# CanBus-Gartenbewaesserung.net
KiCad netlist of a schematic drawn in EAGLE
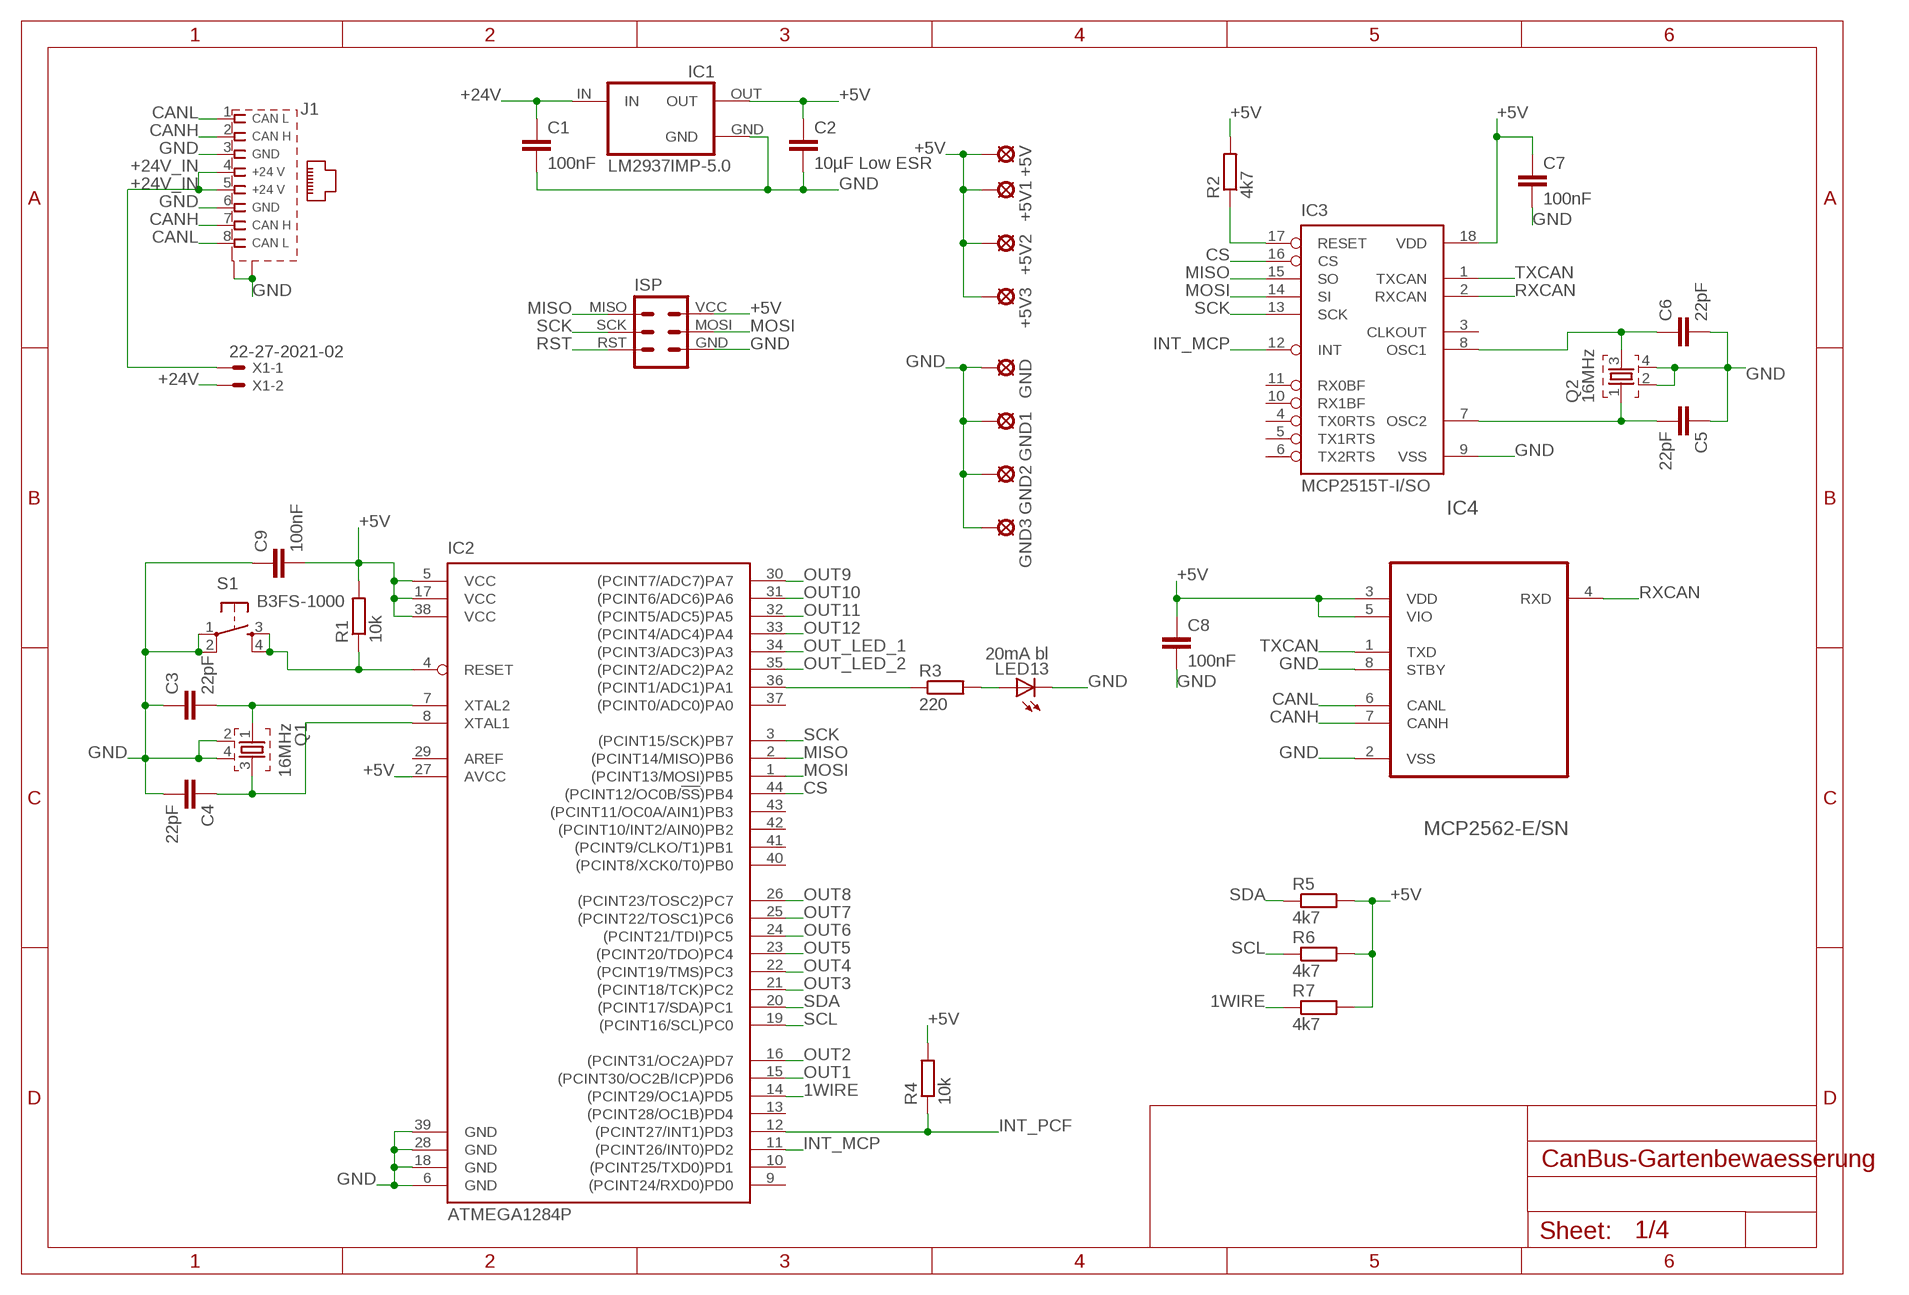
[diagram p0: schematic, sheet 1]
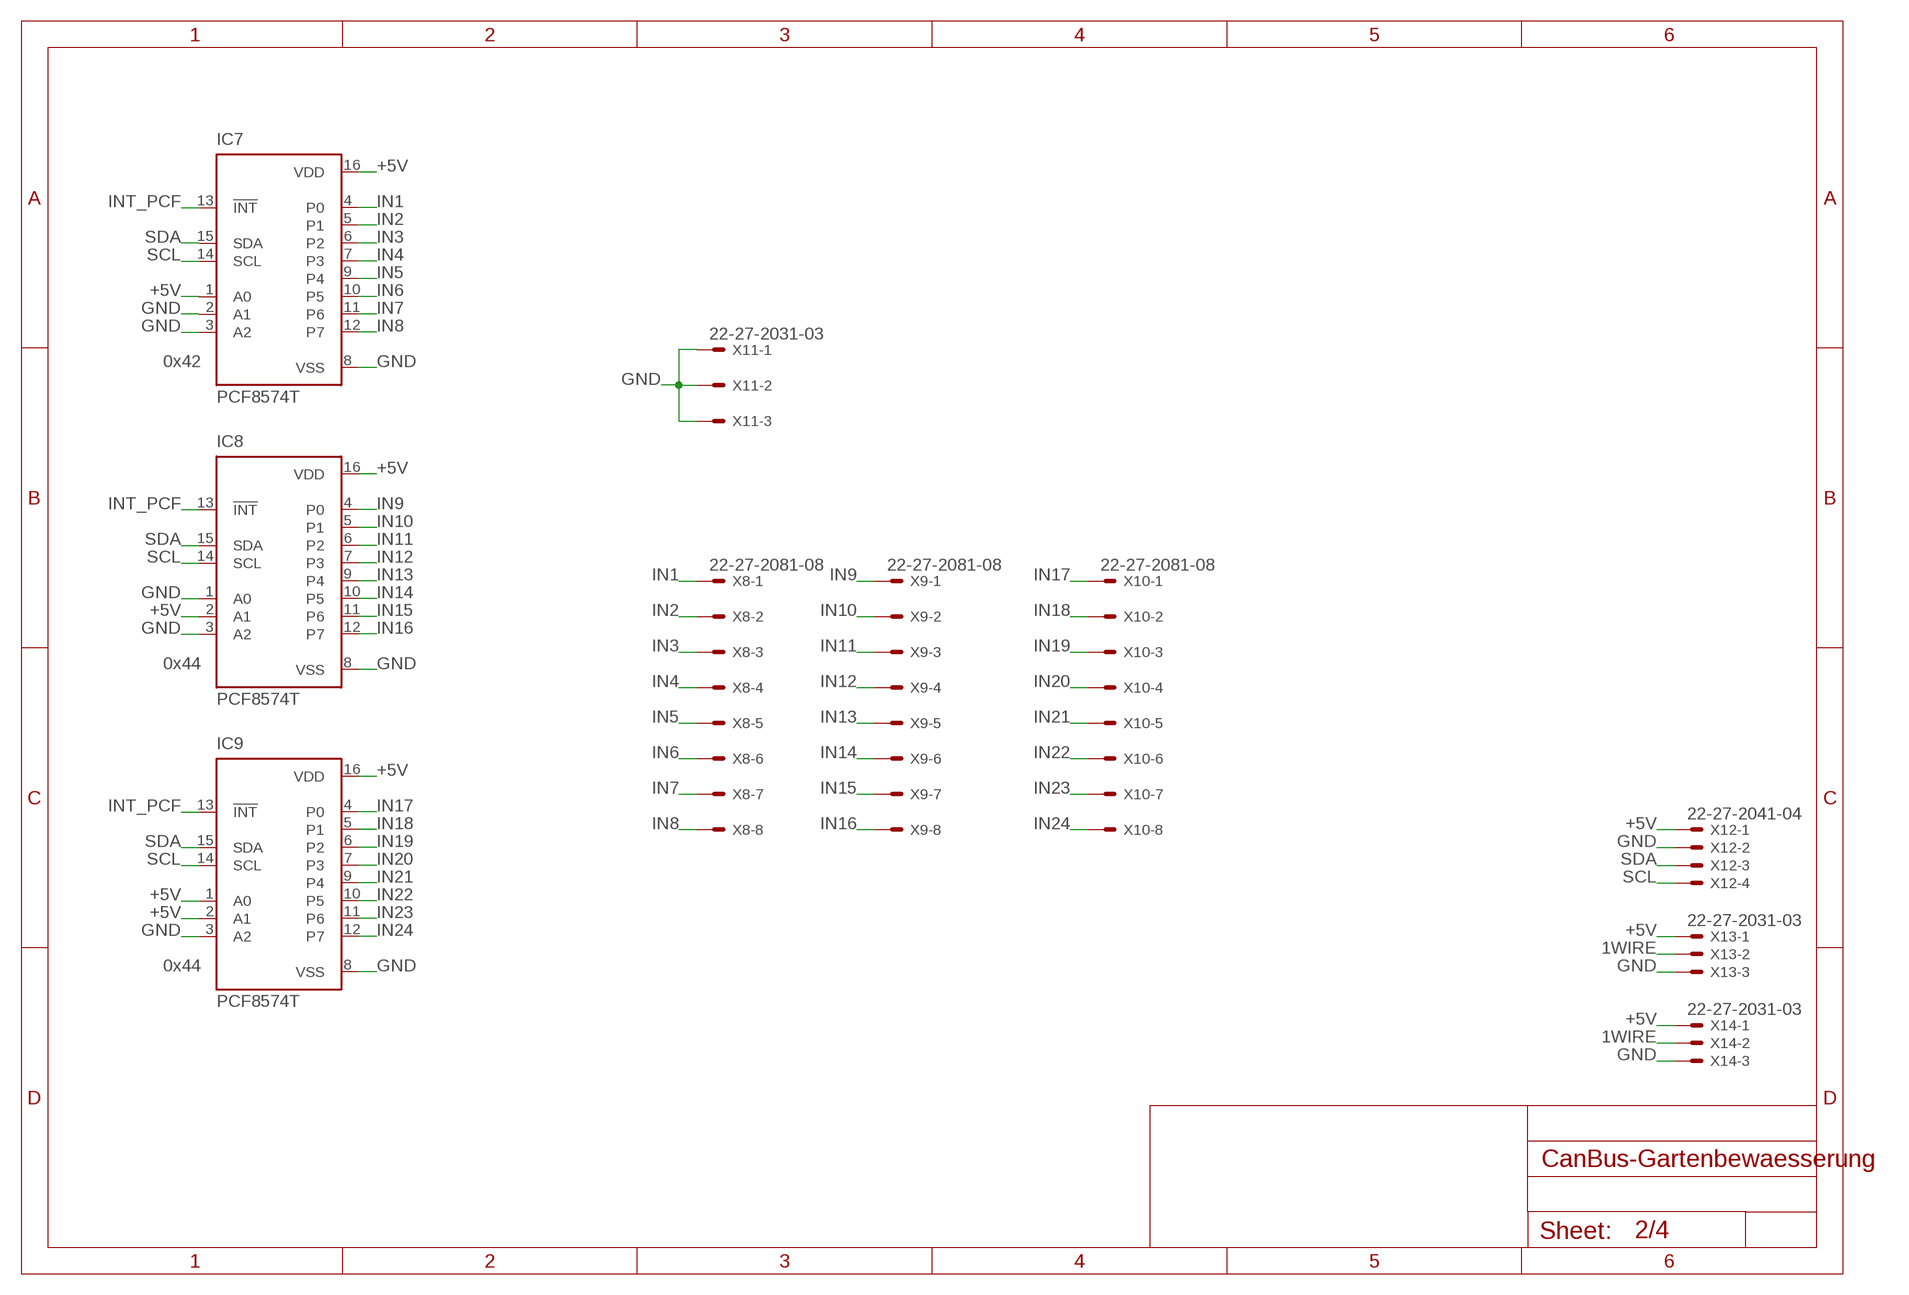
[diagram p1: schematic, sheet 2]
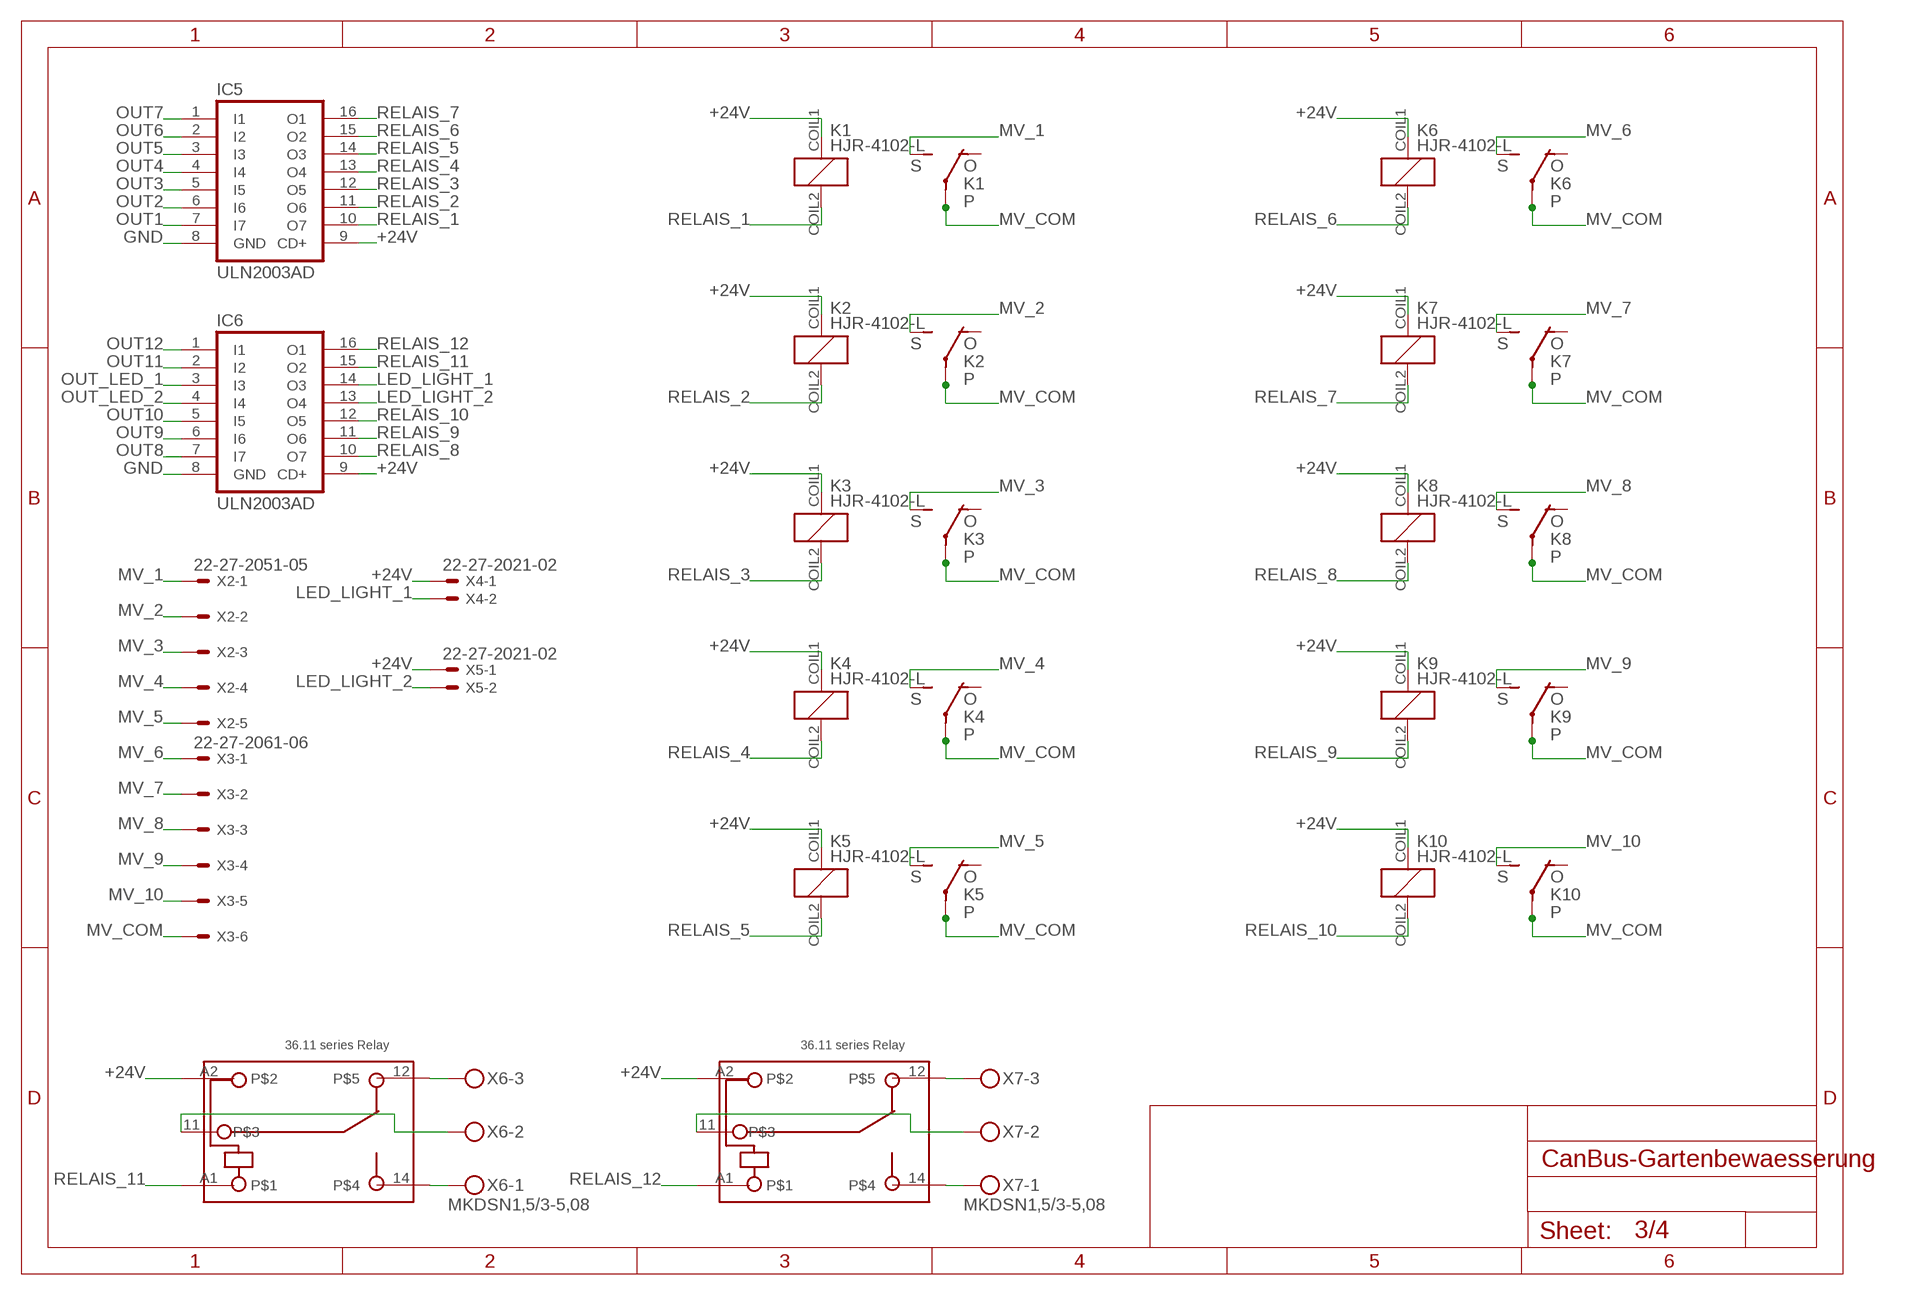
[diagram p2: schematic, sheet 3]
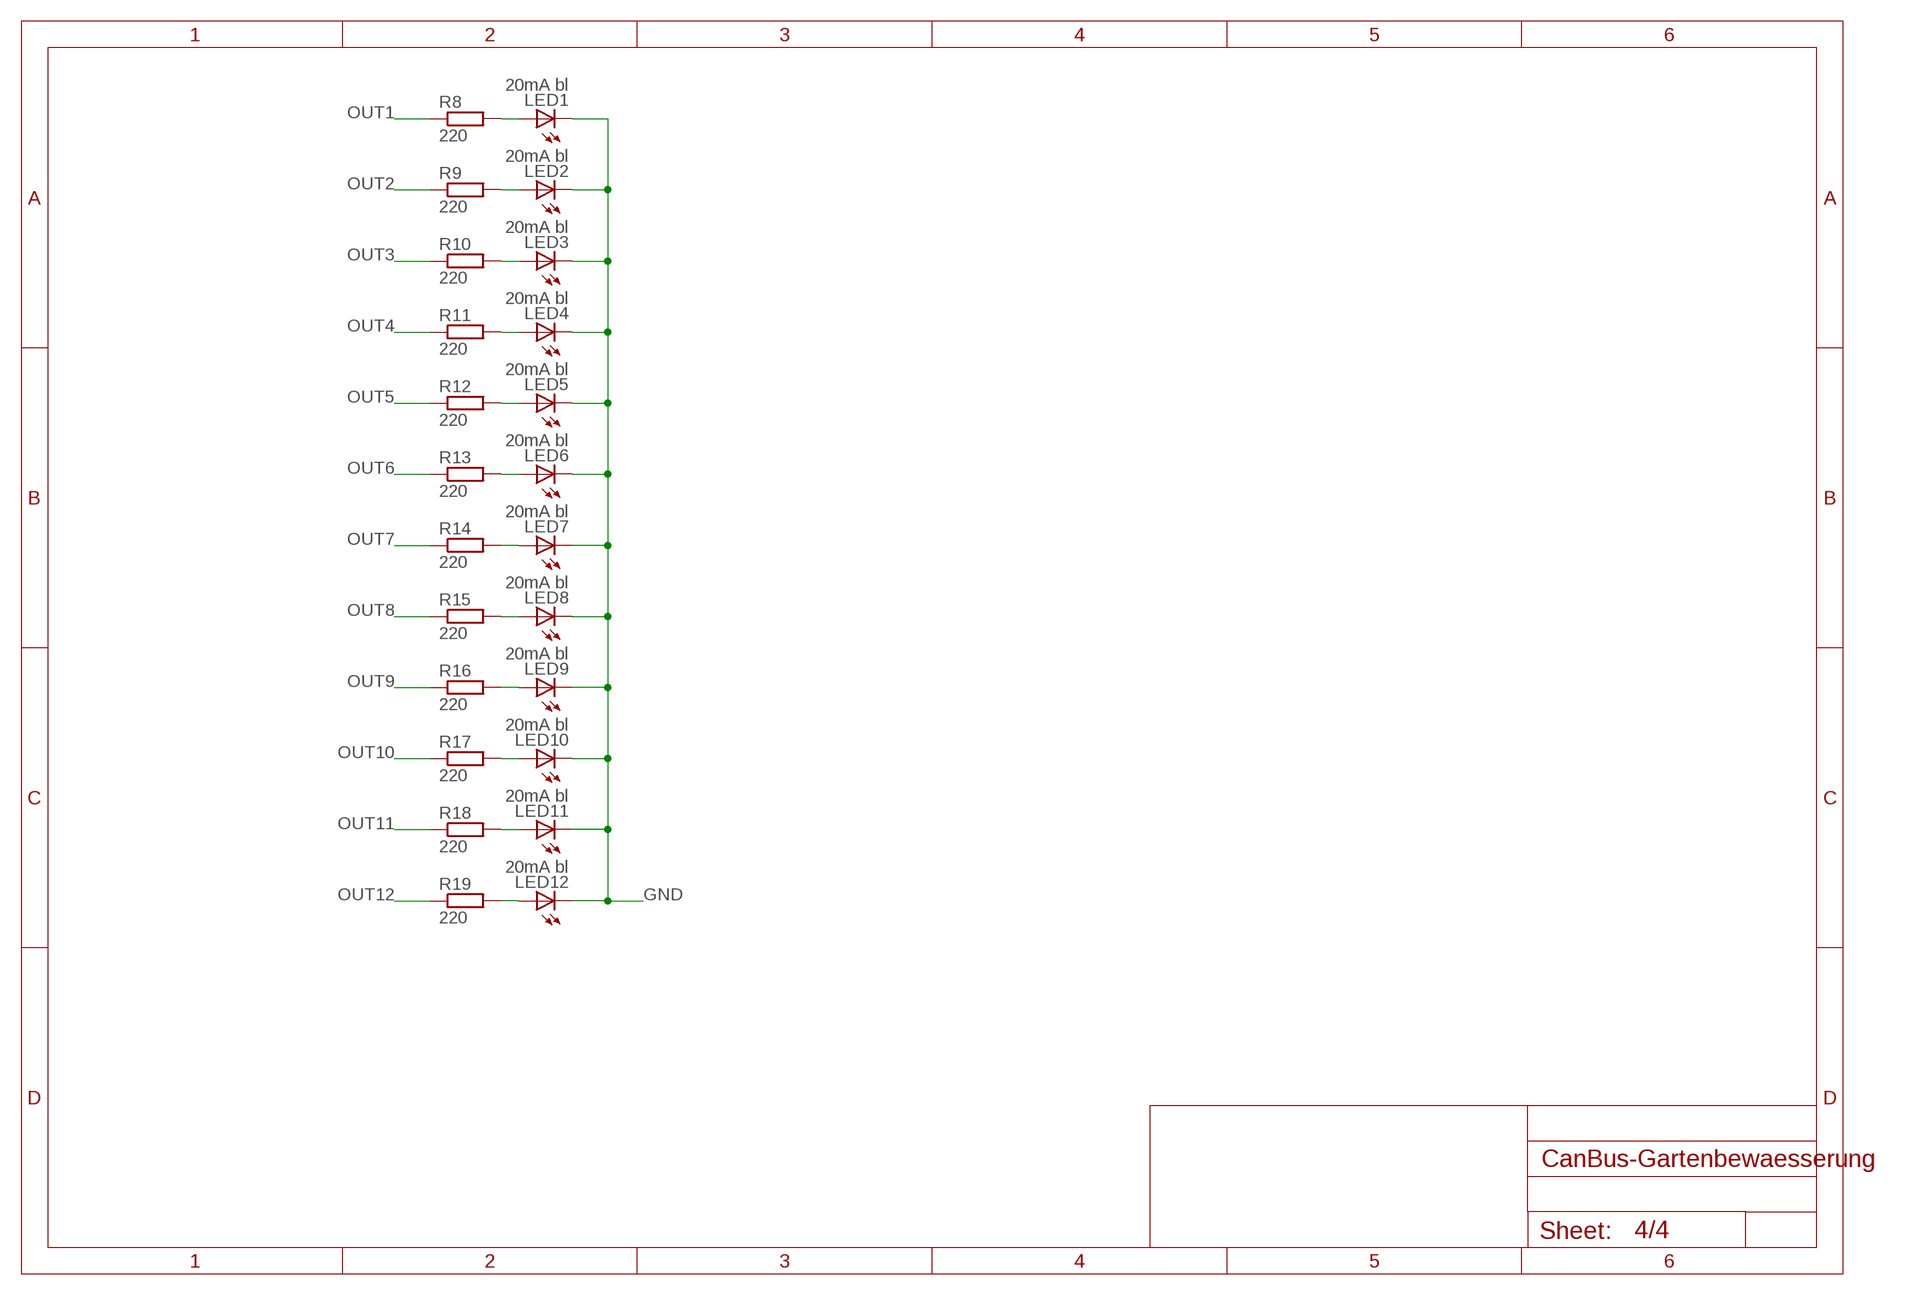
[diagram p3: schematic, sheet 4]

(export (version "E")
  (design (tool "Eeschema 10.0.6"))
  (components
    (comp (ref "LED1")
      (value "20mA bl")
      (footprint "eagle-import:CHIPLED_0805")
      (libsource (lib "eagle-import") (part "LEDCHIPLED_0805"))
    )
    (comp (ref "LED2")
      (value "20mA bl")
      (footprint "eagle-import:CHIPLED_0805")
      (libsource (lib "eagle-import") (part "LEDCHIPLED_0805"))
    )
    (comp (ref "LED3")
      (value "20mA bl")
      (footprint "eagle-import:CHIPLED_0805")
      (libsource (lib "eagle-import") (part "LEDCHIPLED_0805"))
    )
    (comp (ref "LED4")
      (value "20mA bl")
      (footprint "eagle-import:CHIPLED_0805")
      (libsource (lib "eagle-import") (part "LEDCHIPLED_0805"))
    )
    (comp (ref "LED5")
      (value "20mA bl")
      (footprint "eagle-import:CHIPLED_0805")
      (libsource (lib "eagle-import") (part "LEDCHIPLED_0805"))
    )
    (comp (ref "LED6")
      (value "20mA bl")
      (footprint "eagle-import:CHIPLED_0805")
      (libsource (lib "eagle-import") (part "LEDCHIPLED_0805"))
    )
    (comp (ref "LED7")
      (value "20mA bl")
      (footprint "eagle-import:CHIPLED_0805")
      (libsource (lib "eagle-import") (part "LEDCHIPLED_0805"))
    )
    (comp (ref "LED8")
      (value "20mA bl")
      (footprint "eagle-import:CHIPLED_0805")
      (libsource (lib "eagle-import") (part "LEDCHIPLED_0805"))
    )
    (comp (ref "LED9")
      (value "20mA bl")
      (footprint "eagle-import:CHIPLED_0805")
      (libsource (lib "eagle-import") (part "LEDCHIPLED_0805"))
    )
    (comp (ref "LED10")
      (value "20mA bl")
      (footprint "eagle-import:CHIPLED_0805")
      (libsource (lib "eagle-import") (part "LEDCHIPLED_0805"))
    )
    (comp (ref "LED11")
      (value "20mA bl")
      (footprint "eagle-import:CHIPLED_0805")
      (libsource (lib "eagle-import") (part "LEDCHIPLED_0805"))
    )
    (comp (ref "LED12")
      (value "20mA bl")
      (footprint "eagle-import:CHIPLED_0805")
      (libsource (lib "eagle-import") (part "LEDCHIPLED_0805"))
    )
    (comp (ref "R8")
      (value "220")
      (footprint "eagle-import:R0805")
      (libsource (lib "eagle-import") (part "R-EU_R0805"))
    )
    (comp (ref "R9")
      (value "220")
      (footprint "eagle-import:R0805")
      (libsource (lib "eagle-import") (part "R-EU_R0805"))
    )
    (comp (ref "R10")
      (value "220")
      (footprint "eagle-import:R0805")
      (libsource (lib "eagle-import") (part "R-EU_R0805"))
    )
    (comp (ref "R11")
      (value "220")
      (footprint "eagle-import:R0805")
      (libsource (lib "eagle-import") (part "R-EU_R0805"))
    )
    (comp (ref "R12")
      (value "220")
      (footprint "eagle-import:R0805")
      (libsource (lib "eagle-import") (part "R-EU_R0805"))
    )
    (comp (ref "R13")
      (value "220")
      (footprint "eagle-import:R0805")
      (libsource (lib "eagle-import") (part "R-EU_R0805"))
    )
    (comp (ref "R14")
      (value "220")
      (footprint "eagle-import:R0805")
      (libsource (lib "eagle-import") (part "R-EU_R0805"))
    )
    (comp (ref "R15")
      (value "220")
      (footprint "eagle-import:R0805")
      (libsource (lib "eagle-import") (part "R-EU_R0805"))
    )
    (comp (ref "R16")
      (value "220")
      (footprint "eagle-import:R0805")
      (libsource (lib "eagle-import") (part "R-EU_R0805"))
    )
    (comp (ref "R17")
      (value "220")
      (footprint "eagle-import:R0805")
      (libsource (lib "eagle-import") (part "R-EU_R0805"))
    )
    (comp (ref "R18")
      (value "220")
      (footprint "eagle-import:R0805")
      (libsource (lib "eagle-import") (part "R-EU_R0805"))
    )
    (comp (ref "R19")
      (value "220")
      (footprint "eagle-import:R0805")
      (libsource (lib "eagle-import") (part "R-EU_R0805"))
    )
    (comp (ref "IC7")
      (value "PCF8574T")
      (footprint "eagle-import:SO16W")
      (fields (field (name "MPN") "PCF8574T/3,512"))
      (libsource (lib "eagle-import") (part "PCF8574T"))
    )
    (comp (ref "IC8")
      (value "PCF8574T")
      (footprint "eagle-import:SO16W")
      (fields (field (name "MPN") "PCF8574T/3,512"))
      (libsource (lib "eagle-import") (part "PCF8574T"))
    )
    (comp (ref "IC9")
      (value "PCF8574T")
      (footprint "eagle-import:SO16W")
      (fields (field (name "MPN") "PCF8574T/3,512"))
      (libsource (lib "eagle-import") (part "PCF8574T"))
    )
    (comp (ref "X8")
      (value "22-27-2081-08")
      (footprint "eagle-import:6410-08")
      (libsource (lib "eagle-import") (part "22-?-0827-2081"))
    )
    (comp (ref "X9")
      (value "22-27-2081-08")
      (footprint "eagle-import:6410-08")
      (libsource (lib "eagle-import") (part "22-?-0827-2081"))
    )
    (comp (ref "X10")
      (value "22-27-2081-08")
      (footprint "eagle-import:6410-08")
      (libsource (lib "eagle-import") (part "22-?-0827-2081"))
    )
    (comp (ref "X11")
      (value "22-27-2031-03")
      (footprint "eagle-import:6410-03")
      (libsource (lib "eagle-import") (part "22-?-0327-2031"))
    )
    (comp (ref "X12")
      (value "22-27-2041-04")
      (footprint "eagle-import:6410-04")
      (libsource (lib "eagle-import") (part "22-?-0427-2041"))
    )
    (comp (ref "X13")
      (value "22-27-2031-03")
      (footprint "eagle-import:6410-03")
      (libsource (lib "eagle-import") (part "22-?-0327-2031"))
    )
    (comp (ref "X14")
      (value "22-27-2031-03")
      (footprint "eagle-import:6410-03")
      (libsource (lib "eagle-import") (part "22-?-0327-2031"))
    )
    (comp (ref "+5V")
      (value "LSP13")
      (footprint "eagle-import:LSP13")
      (libsource (lib "eagle-import") (part "LSP13"))
    )
    (comp (ref "+5V1")
      (value "LSP13")
      (footprint "eagle-import:LSP13")
      (libsource (lib "eagle-import") (part "LSP13"))
    )
    (comp (ref "+5V2")
      (value "LSP13")
      (footprint "eagle-import:LSP13")
      (libsource (lib "eagle-import") (part "LSP13"))
    )
    (comp (ref "+5V3")
      (value "LSP13")
      (footprint "eagle-import:LSP13")
      (libsource (lib "eagle-import") (part "LSP13"))
    )
    (comp (ref "C1")
      (value "100nF")
      (footprint "eagle-import:C0805")
      (libsource (lib "eagle-import") (part "C-EUC0805"))
    )
    (comp (ref "C2")
      (value "10µF Low ESR")
      (footprint "eagle-import:C0805")
      (libsource (lib "eagle-import") (part "C-EUC0805"))
    )
    (comp (ref "C3")
      (value "22pF")
      (footprint "eagle-import:C0805")
      (libsource (lib "eagle-import") (part "C-EUC0805"))
    )
    (comp (ref "C4")
      (value "22pF")
      (footprint "eagle-import:C0805")
      (libsource (lib "eagle-import") (part "C-EUC0805"))
    )
    (comp (ref "C5")
      (value "22pF")
      (footprint "eagle-import:C0805")
      (libsource (lib "eagle-import") (part "C-EUC0805"))
    )
    (comp (ref "C6")
      (value "22pF")
      (footprint "eagle-import:C0805")
      (libsource (lib "eagle-import") (part "C-EUC0805"))
    )
    (comp (ref "C7")
      (value "100nF")
      (footprint "eagle-import:C0805")
      (libsource (lib "eagle-import") (part "C-EUC0805"))
    )
    (comp (ref "C8")
      (value "100nF")
      (footprint "eagle-import:C0805")
      (libsource (lib "eagle-import") (part "C-EUC0805"))
    )
    (comp (ref "C9")
      (value "100nF")
      (footprint "eagle-import:C0805")
      (libsource (lib "eagle-import") (part "C-EUC0805"))
    )
    (comp (ref "GND")
      (value "LSP13")
      (footprint "eagle-import:LSP13")
      (libsource (lib "eagle-import") (part "LSP13"))
    )
    (comp (ref "GND1")
      (value "LSP13")
      (footprint "eagle-import:LSP13")
      (libsource (lib "eagle-import") (part "LSP13"))
    )
    (comp (ref "GND2")
      (value "LSP13")
      (footprint "eagle-import:LSP13")
      (libsource (lib "eagle-import") (part "LSP13"))
    )
    (comp (ref "GND3")
      (value "LSP13")
      (footprint "eagle-import:LSP13")
      (libsource (lib "eagle-import") (part "LSP13"))
    )
    (comp (ref "IC1")
      (value "LM2937IMP-5.0")
      (footprint "eagle-import:SOT223")
      (libsource (lib "eagle-import") (part "LM2937IMP-5.0"))
    )
    (comp (ref "IC2")
      (value "ATMEGA1284P")
      (footprint "eagle-import:TQFP44")
      (fields (field (name "MPN") "ATMEGA644PV-10AU"))
      (libsource (lib "eagle-import") (part "ATMEGA644A"))
    )
    (comp (ref "IC3")
      (value "MCP2515T-I/SO")
      (footprint "eagle-import:SO18L")
      (libsource (lib "eagle-import") (part "MCP2515T-I/SO"))
    )
    (comp (ref "IC4")
      (value "MCP2562-E/SN")
      (footprint "eagle-import:SO08")
      (libsource (lib "eagle-import") (part "MCP2562-E/SN"))
    )
    (comp (ref "ISP")
      (value "ISPVIAS-ONLY-1.27MM")
      (footprint "eagle-import:ISP-VIAS-ONLY-1.27MM")
      (libsource (lib "eagle-import") (part "ISPVIAS-ONLY-1.27MM"))
    )
    (comp (ref "J1")
      (value "RJ45-CAN")
      (footprint "eagle-import:MEBP_8-8G")
      (libsource (lib "eagle-import") (part "RJ45-CAN"))
    )
    (comp (ref "LED13")
      (value "20mA bl")
      (footprint "eagle-import:CHIPLED_0805")
      (libsource (lib "eagle-import") (part "LEDCHIPLED_0805"))
    )
    (comp (ref "Q1")
      (value "16MHz")
      (footprint "eagle-import:MJ-5X3.2")
      (libsource (lib "eagle-import") (part "EUROQUARTZ-MMJ"))
    )
    (comp (ref "Q2")
      (value "16MHz")
      (footprint "eagle-import:MJ-5X3.2")
      (libsource (lib "eagle-import") (part "EUROQUARTZ-MMJ"))
    )
    (comp (ref "R1")
      (value "10k")
      (footprint "eagle-import:R0805")
      (libsource (lib "eagle-import") (part "R-EU_R0805"))
    )
    (comp (ref "R2")
      (value "4k7")
      (footprint "eagle-import:R0805")
      (libsource (lib "eagle-import") (part "R-EU_R0805"))
    )
    (comp (ref "R3")
      (value "220")
      (footprint "eagle-import:R0805")
      (libsource (lib "eagle-import") (part "R-EU_R0805"))
    )
    (comp (ref "R4")
      (value "10k")
      (footprint "eagle-import:R0805")
      (libsource (lib "eagle-import") (part "R-EU_R0805"))
    )
    (comp (ref "R5")
      (value "4k7")
      (footprint "eagle-import:R0805")
      (libsource (lib "eagle-import") (part "R-EU_R0805"))
    )
    (comp (ref "R6")
      (value "4k7")
      (footprint "eagle-import:R0805")
      (libsource (lib "eagle-import") (part "R-EU_R0805"))
    )
    (comp (ref "R7")
      (value "4k7")
      (footprint "eagle-import:R0805")
      (libsource (lib "eagle-import") (part "R-EU_R0805"))
    )
    (comp (ref "S1")
      (value "B3FS-1000")
      (footprint "eagle-import:B3FS-1000")
      (libsource (lib "eagle-import") (part "B3FS-1000"))
    )
    (comp (ref "X1")
      (value "22-27-2021-02")
      (footprint "eagle-import:6410-02")
      (libsource (lib "eagle-import") (part "22-?-0227-2021"))
    )
    (comp (ref "IC5")
      (value "ULN2003AD")
      (footprint "eagle-import:SO16")
      (libsource (lib "eagle-import") (part "ULN2003AD"))
    )
    (comp (ref "IC6")
      (value "ULN2003AD")
      (footprint "eagle-import:SO16")
      (libsource (lib "eagle-import") (part "ULN2003AD"))
    )
    (comp (ref "K1")
      (value "HJR-4102-L")
      (footprint "eagle-import:HJR4102")
      (libsource (lib "eagle-import") (part "HJR-4102-L"))
    )
    (comp (ref "K2")
      (value "HJR-4102-L")
      (footprint "eagle-import:HJR4102")
      (libsource (lib "eagle-import") (part "HJR-4102-L"))
    )
    (comp (ref "K3")
      (value "HJR-4102-L")
      (footprint "eagle-import:HJR4102")
      (libsource (lib "eagle-import") (part "HJR-4102-L"))
    )
    (comp (ref "K4")
      (value "HJR-4102-L")
      (footprint "eagle-import:HJR4102")
      (libsource (lib "eagle-import") (part "HJR-4102-L"))
    )
    (comp (ref "K5")
      (value "HJR-4102-L")
      (footprint "eagle-import:HJR4102")
      (libsource (lib "eagle-import") (part "HJR-4102-L"))
    )
    (comp (ref "K6")
      (value "HJR-4102-L")
      (footprint "eagle-import:HJR4102")
      (libsource (lib "eagle-import") (part "HJR-4102-L"))
    )
    (comp (ref "K7")
      (value "HJR-4102-L")
      (footprint "eagle-import:HJR4102")
      (libsource (lib "eagle-import") (part "HJR-4102-L"))
    )
    (comp (ref "K8")
      (value "HJR-4102-L")
      (footprint "eagle-import:HJR4102")
      (libsource (lib "eagle-import") (part "HJR-4102-L"))
    )
    (comp (ref "K9")
      (value "HJR-4102-L")
      (footprint "eagle-import:HJR4102")
      (libsource (lib "eagle-import") (part "HJR-4102-L"))
    )
    (comp (ref "K10")
      (value "HJR-4102-L")
      (footprint "eagle-import:HJR4102")
      (libsource (lib "eagle-import") (part "HJR-4102-L"))
    )
    (comp (ref "K11")
      (value "36.11")
      (footprint "eagle-import:36.11")
      (libsource (lib "eagle-import") (part "36.11"))
    )
    (comp (ref "K12")
      (value "36.11")
      (footprint "eagle-import:36.11")
      (libsource (lib "eagle-import") (part "36.11"))
    )
    (comp (ref "X2")
      (value "22-27-2051-05")
      (footprint "eagle-import:6410-05")
      (libsource (lib "eagle-import") (part "22-?-0527-2051"))
    )
    (comp (ref "X3")
      (value "22-27-2061-06")
      (footprint "eagle-import:6410-06")
      (libsource (lib "eagle-import") (part "22-?-0627-2061"))
    )
    (comp (ref "X4")
      (value "22-27-2021-02")
      (footprint "eagle-import:6410-02")
      (libsource (lib "eagle-import") (part "22-?-0227-2021"))
    )
    (comp (ref "X5")
      (value "22-27-2021-02")
      (footprint "eagle-import:6410-02")
      (libsource (lib "eagle-import") (part "22-?-0227-2021"))
    )
    (comp (ref "X6")
      (value "MKDSN1,5/3-5,08")
      (footprint "eagle-import:MKDSN1,5_3-5,08")
      (libsource (lib "eagle-import") (part "MKDSN1,5/3-5,08"))
    )
    (comp (ref "X7")
      (value "MKDSN1,5/3-5,08")
      (footprint "eagle-import:MKDSN1,5_3-5,08")
      (libsource (lib "eagle-import") (part "MKDSN1,5/3-5,08"))
    )
  )
  (nets
    (net (code "1") (name "+5V") (class "Default")
      (node (ref "+5V") (pin "MP") (pinfunction "MP_MP") (pintype "passive"))
      (node (ref "+5V1") (pin "MP") (pinfunction "MP_MP") (pintype "passive"))
      (node (ref "+5V2") (pin "MP") (pinfunction "MP_MP") (pintype "passive"))
      (node (ref "+5V3") (pin "MP") (pinfunction "MP_MP") (pintype "passive"))
      (node (ref "C2") (pin "1") (pinfunction "1_1") (pintype "passive"))
      (node (ref "C7") (pin "1") (pinfunction "1_1") (pintype "passive"))
      (node (ref "C8") (pin "1") (pinfunction "1_1") (pintype "passive"))
      (node (ref "C9") (pin "2") (pinfunction "2_2") (pintype "passive"))
      (node (ref "IC1") (pin "OUT") (pinfunction "OUT_OUT") (pintype "output"))
      (node (ref "IC2") (pin "17") (pinfunction "VCC_17") (pintype "power_in"))
      (node (ref "IC2") (pin "27") (pinfunction "AVCC_27") (pintype "power_in"))
      (node (ref "IC2") (pin "38") (pinfunction "VCC_38") (pintype "power_in"))
      (node (ref "IC2") (pin "5") (pinfunction "VCC_5") (pintype "power_in"))
      (node (ref "IC3") (pin "18") (pinfunction "VDD_18") (pintype "power_in"))
      (node (ref "IC4") (pin "3") (pinfunction "VDD_3") (pintype "power_in"))
      (node (ref "IC4") (pin "5") (pinfunction "VIO_5") (pintype "power_in"))
      (node (ref "IC7") (pin "1") (pinfunction "A0_1") (pintype "input"))
      (node (ref "IC7") (pin "16") (pinfunction "VDD_16") (pintype "power_in"))
      (node (ref "IC8") (pin "16") (pinfunction "VDD_16") (pintype "power_in"))
      (node (ref "IC8") (pin "2") (pinfunction "A1_2") (pintype "input"))
      (node (ref "IC9") (pin "1") (pinfunction "A0_1") (pintype "input"))
      (node (ref "IC9") (pin "16") (pinfunction "VDD_16") (pintype "power_in"))
      (node (ref "IC9") (pin "2") (pinfunction "A1_2") (pintype "input"))
      (node (ref "ISP") (pin "VCC") (pinfunction "VCC_VCC") (pintype "passive"))
      (node (ref "R1") (pin "2") (pinfunction "2_2") (pintype "passive"))
      (node (ref "R2") (pin "2") (pinfunction "2_2") (pintype "passive"))
      (node (ref "R4") (pin "2") (pinfunction "2_2") (pintype "passive"))
      (node (ref "R5") (pin "2") (pinfunction "2_2") (pintype "passive"))
      (node (ref "R6") (pin "2") (pinfunction "2_2") (pintype "passive"))
      (node (ref "R7") (pin "2") (pinfunction "2_2") (pintype "passive"))
      (node (ref "X12") (pin "1") (pinfunction "S_1") (pintype "passive"))
      (node (ref "X13") (pin "1") (pinfunction "S_1") (pintype "passive"))
      (node (ref "X14") (pin "1") (pinfunction "S_1") (pintype "passive"))
    )
    (net (code "2") (name "+24V") (class "Default")
      (node (ref "C1") (pin "1") (pinfunction "1_1") (pintype "passive"))
      (node (ref "IC1") (pin "IN") (pinfunction "IN_IN") (pintype "input"))
      (node (ref "IC5") (pin "9") (pinfunction "CD+_9") (pintype "passive"))
      (node (ref "IC6") (pin "9") (pinfunction "CD+_9") (pintype "passive"))
      (node (ref "K1") (pin "COIL1") (pinfunction "1_COIL1") (pintype "passive"))
      (node (ref "K10") (pin "COIL1") (pinfunction "1_COIL1") (pintype "passive"))
      (node (ref "K11") (pin "A2") (pinfunction "P$2_A2") (pintype "passive"))
      (node (ref "K12") (pin "A2") (pinfunction "P$2_A2") (pintype "passive"))
      (node (ref "K2") (pin "COIL1") (pinfunction "1_COIL1") (pintype "passive"))
      (node (ref "K3") (pin "COIL1") (pinfunction "1_COIL1") (pintype "passive"))
      (node (ref "K4") (pin "COIL1") (pinfunction "1_COIL1") (pintype "passive"))
      (node (ref "K5") (pin "COIL1") (pinfunction "1_COIL1") (pintype "passive"))
      (node (ref "K6") (pin "COIL1") (pinfunction "1_COIL1") (pintype "passive"))
      (node (ref "K7") (pin "COIL1") (pinfunction "1_COIL1") (pintype "passive"))
      (node (ref "K8") (pin "COIL1") (pinfunction "1_COIL1") (pintype "passive"))
      (node (ref "K9") (pin "COIL1") (pinfunction "1_COIL1") (pintype "passive"))
      (node (ref "X1") (pin "2") (pinfunction "S_2") (pintype "passive"))
      (node (ref "X4") (pin "1") (pinfunction "S_1") (pintype "passive"))
      (node (ref "X5") (pin "1") (pinfunction "S_1") (pintype "passive"))
    )
    (net (code "3") (name "+24V_IN") (class "Default")
      (node (ref "J1") (pin "4") (pinfunction "4_4") (pintype "passive"))
      (node (ref "J1") (pin "5") (pinfunction "5_5") (pintype "passive"))
      (node (ref "X1") (pin "1") (pinfunction "S_1") (pintype "passive"))
    )
    (net (code "4") (name "1WIRE") (class "Default")
      (node (ref "IC2") (pin "14") (pinfunction "(PCINT29/OC1A)PD5_14") (pintype "bidirectional"))
      (node (ref "R7") (pin "1") (pinfunction "1_1") (pintype "passive"))
      (node (ref "X13") (pin "2") (pinfunction "S_2") (pintype "passive"))
      (node (ref "X14") (pin "2") (pinfunction "S_2") (pintype "passive"))
    )
    (net (code "5") (name "CANH") (class "Default")
      (node (ref "IC4") (pin "7") (pinfunction "CANH_7") (pintype "bidirectional"))
      (node (ref "J1") (pin "2") (pinfunction "2_2") (pintype "passive"))
      (node (ref "J1") (pin "7") (pinfunction "7_7") (pintype "passive"))
    )
    (net (code "6") (name "CANL") (class "Default")
      (node (ref "IC4") (pin "6") (pinfunction "CANL_6") (pintype "bidirectional"))
      (node (ref "J1") (pin "1") (pinfunction "1_1") (pintype "passive"))
      (node (ref "J1") (pin "8") (pinfunction "8_8") (pintype "passive"))
    )
    (net (code "7") (name "CS") (class "Default")
      (node (ref "IC2") (pin "44") (pinfunction "(PCINT12/OC0B/~{SS})PB4_44") (pintype "bidirectional"))
      (node (ref "IC3") (pin "16") (pinfunction "CS_16") (pintype "input"))
    )
    (net (code "8") (name "GND") (class "Default")
      (node (ref "C1") (pin "2") (pinfunction "2_2") (pintype "passive"))
      (node (ref "C2") (pin "2") (pinfunction "2_2") (pintype "passive"))
      (node (ref "C3") (pin "1") (pinfunction "1_1") (pintype "passive"))
      (node (ref "C4") (pin "2") (pinfunction "2_2") (pintype "passive"))
      (node (ref "C5") (pin "1") (pinfunction "1_1") (pintype "passive"))
      (node (ref "C6") (pin "2") (pinfunction "2_2") (pintype "passive"))
      (node (ref "C7") (pin "2") (pinfunction "2_2") (pintype "passive"))
      (node (ref "C8") (pin "2") (pinfunction "2_2") (pintype "passive"))
      (node (ref "C9") (pin "1") (pinfunction "1_1") (pintype "passive"))
      (node (ref "GND") (pin "MP") (pinfunction "MP_MP") (pintype "passive"))
      (node (ref "GND1") (pin "MP") (pinfunction "MP_MP") (pintype "passive"))
      (node (ref "GND2") (pin "MP") (pinfunction "MP_MP") (pintype "passive"))
      (node (ref "GND3") (pin "MP") (pinfunction "MP_MP") (pintype "passive"))
      (node (ref "IC1") (pin "GND") (pinfunction "GND_GND") (pintype "power_in"))
      (node (ref "IC2") (pin "18") (pinfunction "GND_18") (pintype "power_in"))
      (node (ref "IC2") (pin "28") (pinfunction "GND_28") (pintype "power_in"))
      (node (ref "IC2") (pin "39") (pinfunction "GND_39") (pintype "power_in"))
      (node (ref "IC2") (pin "6") (pinfunction "GND_6") (pintype "power_in"))
      (node (ref "IC3") (pin "9") (pinfunction "VSS_9") (pintype "power_in"))
      (node (ref "IC4") (pin "2") (pinfunction "VSS_2") (pintype "power_in"))
      (node (ref "IC4") (pin "8") (pinfunction "STBY_8") (pintype "input"))
      (node (ref "IC5") (pin "8") (pinfunction "GND_8") (pintype "power_in"))
      (node (ref "IC6") (pin "8") (pinfunction "GND_8") (pintype "power_in"))
      (node (ref "IC7") (pin "2") (pinfunction "A1_2") (pintype "input"))
      (node (ref "IC7") (pin "3") (pinfunction "A2_3") (pintype "input"))
      (node (ref "IC7") (pin "8") (pinfunction "VSS_8") (pintype "power_in"))
      (node (ref "IC8") (pin "1") (pinfunction "A0_1") (pintype "input"))
      (node (ref "IC8") (pin "3") (pinfunction "A2_3") (pintype "input"))
      (node (ref "IC8") (pin "8") (pinfunction "VSS_8") (pintype "power_in"))
      (node (ref "IC9") (pin "3") (pinfunction "A2_3") (pintype "input"))
      (node (ref "IC9") (pin "8") (pinfunction "VSS_8") (pintype "power_in"))
      (node (ref "ISP") (pin "GND") (pinfunction "GND_GND") (pintype "passive"))
      (node (ref "J1") (pin "3") (pinfunction "3_3") (pintype "passive"))
      (node (ref "J1") (pin "6") (pinfunction "6_6") (pintype "passive"))
      (node (ref "J1") (pin "G1") (pinfunction "S1_G1") (pintype "passive"))
      (node (ref "J1") (pin "G2") (pinfunction "S2_G2") (pintype "passive"))
      (node (ref "LED1") (pin "C") (pinfunction "C_C") (pintype "passive"))
      (node (ref "LED10") (pin "C") (pinfunction "C_C") (pintype "passive"))
      (node (ref "LED11") (pin "C") (pinfunction "C_C") (pintype "passive"))
      (node (ref "LED12") (pin "C") (pinfunction "C_C") (pintype "passive"))
      (node (ref "LED13") (pin "C") (pinfunction "C_C") (pintype "passive"))
      (node (ref "LED2") (pin "C") (pinfunction "C_C") (pintype "passive"))
      (node (ref "LED3") (pin "C") (pinfunction "C_C") (pintype "passive"))
      (node (ref "LED4") (pin "C") (pinfunction "C_C") (pintype "passive"))
      (node (ref "LED5") (pin "C") (pinfunction "C_C") (pintype "passive"))
      (node (ref "LED6") (pin "C") (pinfunction "C_C") (pintype "passive"))
      (node (ref "LED7") (pin "C") (pinfunction "C_C") (pintype "passive"))
      (node (ref "LED8") (pin "C") (pinfunction "C_C") (pintype "passive"))
      (node (ref "LED9") (pin "C") (pinfunction "C_C") (pintype "passive"))
      (node (ref "Q1") (pin "2") (pinfunction "2_2") (pintype "passive"))
      (node (ref "Q1") (pin "4") (pinfunction "4_4") (pintype "passive"))
      (node (ref "Q2") (pin "2") (pinfunction "2_2") (pintype "passive"))
      (node (ref "Q2") (pin "4") (pinfunction "4_4") (pintype "passive"))
      (node (ref "S1") (pin "1") (pinfunction "P_1") (pintype "passive"))
      (node (ref "S1") (pin "2") (pinfunction "P1_2") (pintype "passive"))
      (node (ref "X11") (pin "1") (pinfunction "S_1") (pintype "passive"))
      (node (ref "X11") (pin "2") (pinfunction "S_2") (pintype "passive"))
      (node (ref "X11") (pin "3") (pinfunction "S_3") (pintype "passive"))
      (node (ref "X12") (pin "2") (pinfunction "S_2") (pintype "passive"))
      (node (ref "X13") (pin "3") (pinfunction "S_3") (pintype "passive"))
      (node (ref "X14") (pin "3") (pinfunction "S_3") (pintype "passive"))
    )
    (net (code "9") (name "IN1") (class "Default")
      (node (ref "IC7") (pin "4") (pinfunction "P0_4") (pintype "bidirectional"))
      (node (ref "X8") (pin "1") (pinfunction "S_1") (pintype "passive"))
    )
    (net (code "10") (name "IN2") (class "Default")
      (node (ref "IC7") (pin "5") (pinfunction "P1_5") (pintype "bidirectional"))
      (node (ref "X8") (pin "2") (pinfunction "S_2") (pintype "passive"))
    )
    (net (code "11") (name "IN3") (class "Default")
      (node (ref "IC7") (pin "6") (pinfunction "P2_6") (pintype "bidirectional"))
      (node (ref "X8") (pin "3") (pinfunction "S_3") (pintype "passive"))
    )
    (net (code "12") (name "IN4") (class "Default")
      (node (ref "IC7") (pin "7") (pinfunction "P3_7") (pintype "bidirectional"))
      (node (ref "X8") (pin "4") (pinfunction "S_4") (pintype "passive"))
    )
    (net (code "13") (name "IN5") (class "Default")
      (node (ref "IC7") (pin "9") (pinfunction "P4_9") (pintype "bidirectional"))
      (node (ref "X8") (pin "5") (pinfunction "S_5") (pintype "passive"))
    )
    (net (code "14") (name "IN6") (class "Default")
      (node (ref "IC7") (pin "10") (pinfunction "P5_10") (pintype "bidirectional"))
      (node (ref "X8") (pin "6") (pinfunction "S_6") (pintype "passive"))
    )
    (net (code "15") (name "IN7") (class "Default")
      (node (ref "IC7") (pin "11") (pinfunction "P6_11") (pintype "bidirectional"))
      (node (ref "X8") (pin "7") (pinfunction "S_7") (pintype "passive"))
    )
    (net (code "16") (name "IN8") (class "Default")
      (node (ref "IC7") (pin "12") (pinfunction "P7_12") (pintype "bidirectional"))
      (node (ref "X8") (pin "8") (pinfunction "S_8") (pintype "passive"))
    )
    (net (code "17") (name "IN9") (class "Default")
      (node (ref "IC8") (pin "4") (pinfunction "P0_4") (pintype "bidirectional"))
      (node (ref "X9") (pin "1") (pinfunction "S_1") (pintype "passive"))
    )
    (net (code "18") (name "IN10") (class "Default")
      (node (ref "IC8") (pin "5") (pinfunction "P1_5") (pintype "bidirectional"))
      (node (ref "X9") (pin "2") (pinfunction "S_2") (pintype "passive"))
    )
    (net (code "19") (name "IN11") (class "Default")
      (node (ref "IC8") (pin "6") (pinfunction "P2_6") (pintype "bidirectional"))
      (node (ref "X9") (pin "3") (pinfunction "S_3") (pintype "passive"))
    )
    (net (code "20") (name "IN12") (class "Default")
      (node (ref "IC8") (pin "7") (pinfunction "P3_7") (pintype "bidirectional"))
      (node (ref "X9") (pin "4") (pinfunction "S_4") (pintype "passive"))
    )
    (net (code "21") (name "IN13") (class "Default")
      (node (ref "IC8") (pin "9") (pinfunction "P4_9") (pintype "bidirectional"))
      (node (ref "X9") (pin "5") (pinfunction "S_5") (pintype "passive"))
    )
    (net (code "22") (name "IN14") (class "Default")
      (node (ref "IC8") (pin "10") (pinfunction "P5_10") (pintype "bidirectional"))
      (node (ref "X9") (pin "6") (pinfunction "S_6") (pintype "passive"))
    )
    (net (code "23") (name "IN15") (class "Default")
      (node (ref "IC8") (pin "11") (pinfunction "P6_11") (pintype "bidirectional"))
      (node (ref "X9") (pin "7") (pinfunction "S_7") (pintype "passive"))
    )
    (net (code "24") (name "IN16") (class "Default")
      (node (ref "IC8") (pin "12") (pinfunction "P7_12") (pintype "bidirectional"))
      (node (ref "X9") (pin "8") (pinfunction "S_8") (pintype "passive"))
    )
    (net (code "25") (name "IN17") (class "Default")
      (node (ref "IC9") (pin "4") (pinfunction "P0_4") (pintype "bidirectional"))
      (node (ref "X10") (pin "1") (pinfunction "S_1") (pintype "passive"))
    )
    (net (code "26") (name "IN18") (class "Default")
      (node (ref "IC9") (pin "5") (pinfunction "P1_5") (pintype "bidirectional"))
      (node (ref "X10") (pin "2") (pinfunction "S_2") (pintype "passive"))
    )
    (net (code "27") (name "IN19") (class "Default")
      (node (ref "IC9") (pin "6") (pinfunction "P2_6") (pintype "bidirectional"))
      (node (ref "X10") (pin "3") (pinfunction "S_3") (pintype "passive"))
    )
    (net (code "28") (name "IN20") (class "Default")
      (node (ref "IC9") (pin "7") (pinfunction "P3_7") (pintype "bidirectional"))
      (node (ref "X10") (pin "4") (pinfunction "S_4") (pintype "passive"))
    )
    (net (code "29") (name "IN21") (class "Default")
      (node (ref "IC9") (pin "9") (pinfunction "P4_9") (pintype "bidirectional"))
      (node (ref "X10") (pin "5") (pinfunction "S_5") (pintype "passive"))
    )
    (net (code "30") (name "IN22") (class "Default")
      (node (ref "IC9") (pin "10") (pinfunction "P5_10") (pintype "bidirectional"))
      (node (ref "X10") (pin "6") (pinfunction "S_6") (pintype "passive"))
    )
    (net (code "31") (name "IN23") (class "Default")
      (node (ref "IC9") (pin "11") (pinfunction "P6_11") (pintype "bidirectional"))
      (node (ref "X10") (pin "7") (pinfunction "S_7") (pintype "passive"))
    )
    (net (code "32") (name "IN24") (class "Default")
      (node (ref "IC9") (pin "12") (pinfunction "P7_12") (pintype "bidirectional"))
      (node (ref "X10") (pin "8") (pinfunction "S_8") (pintype "passive"))
    )
    (net (code "33") (name "INT_MCP") (class "Default")
      (node (ref "IC2") (pin "11") (pinfunction "(PCINT26/INT0)PD2_11") (pintype "bidirectional"))
      (node (ref "IC3") (pin "12") (pinfunction "INT_12") (pintype "output"))
    )
    (net (code "34") (name "INT_PCF") (class "Default")
      (node (ref "IC2") (pin "12") (pinfunction "(PCINT27/INT1)PD3_12") (pintype "bidirectional"))
      (node (ref "IC7") (pin "13") (pinfunction "~{INT}_13") (pintype "output"))
      (node (ref "IC8") (pin "13") (pinfunction "~{INT}_13") (pintype "output"))
      (node (ref "IC9") (pin "13") (pinfunction "~{INT}_13") (pintype "output"))
      (node (ref "R4") (pin "1") (pinfunction "1_1") (pintype "passive"))
    )
    (net (code "35") (name "LED_LIGHT_1") (class "Default")
      (node (ref "IC6") (pin "14") (pinfunction "O3_14") (pintype "open_collector"))
      (node (ref "X4") (pin "2") (pinfunction "S_2") (pintype "passive"))
    )
    (net (code "36") (name "LED_LIGHT_2") (class "Default")
      (node (ref "IC6") (pin "13") (pinfunction "O4_13") (pintype "open_collector"))
      (node (ref "X5") (pin "2") (pinfunction "S_2") (pintype "passive"))
    )
    (net (code "37") (name "MISO") (class "Default")
      (node (ref "IC2") (pin "2") (pinfunction "(PCINT14/MISO)PB6_2") (pintype "bidirectional"))
      (node (ref "IC3") (pin "15") (pinfunction "SO_15") (pintype "output"))
      (node (ref "ISP") (pin "MISO") (pinfunction "MISO_MISO") (pintype "passive"))
    )
    (net (code "38") (name "MOSI") (class "Default")
      (node (ref "IC2") (pin "1") (pinfunction "(PCINT13/MOSI)PB5_1") (pintype "bidirectional"))
      (node (ref "IC3") (pin "14") (pinfunction "SI_14") (pintype "input"))
      (node (ref "ISP") (pin "MOSI") (pinfunction "MOSI_MOSI") (pintype "passive"))
    )
    (net (code "39") (name "MV_1") (class "Default")
      (node (ref "K1") (pin "CON1DEFAULT") (pinfunction "S_CON1DEFAULT") (pintype "passive"))
      (node (ref "X2") (pin "1") (pinfunction "S_1") (pintype "passive"))
    )
    (net (code "40") (name "MV_2") (class "Default")
      (node (ref "K2") (pin "CON1DEFAULT") (pinfunction "S_CON1DEFAULT") (pintype "passive"))
      (node (ref "X2") (pin "2") (pinfunction "S_2") (pintype "passive"))
    )
    (net (code "41") (name "MV_3") (class "Default")
      (node (ref "K3") (pin "CON1DEFAULT") (pinfunction "S_CON1DEFAULT") (pintype "passive"))
      (node (ref "X2") (pin "3") (pinfunction "S_3") (pintype "passive"))
    )
    (net (code "42") (name "MV_4") (class "Default")
      (node (ref "K4") (pin "CON1DEFAULT") (pinfunction "S_CON1DEFAULT") (pintype "passive"))
      (node (ref "X2") (pin "4") (pinfunction "S_4") (pintype "passive"))
    )
    (net (code "43") (name "MV_5") (class "Default")
      (node (ref "K5") (pin "CON1DEFAULT") (pinfunction "S_CON1DEFAULT") (pintype "passive"))
      (node (ref "X2") (pin "5") (pinfunction "S_5") (pintype "passive"))
    )
    (net (code "44") (name "MV_6") (class "Default")
      (node (ref "K6") (pin "CON1DEFAULT") (pinfunction "S_CON1DEFAULT") (pintype "passive"))
      (node (ref "X3") (pin "1") (pinfunction "S_1") (pintype "passive"))
    )
    (net (code "45") (name "MV_7") (class "Default")
      (node (ref "K7") (pin "CON1DEFAULT") (pinfunction "S_CON1DEFAULT") (pintype "passive"))
      (node (ref "X3") (pin "2") (pinfunction "S_2") (pintype "passive"))
    )
    (net (code "46") (name "MV_8") (class "Default")
      (node (ref "K8") (pin "CON1DEFAULT") (pinfunction "S_CON1DEFAULT") (pintype "passive"))
      (node (ref "X3") (pin "3") (pinfunction "S_3") (pintype "passive"))
    )
    (net (code "47") (name "MV_9") (class "Default")
      (node (ref "K9") (pin "CON1DEFAULT") (pinfunction "S_CON1DEFAULT") (pintype "passive"))
      (node (ref "X3") (pin "4") (pinfunction "S_4") (pintype "passive"))
    )
    (net (code "48") (name "MV_10") (class "Default")
      (node (ref "K10") (pin "CON1DEFAULT") (pinfunction "S_CON1DEFAULT") (pintype "passive"))
      (node (ref "X3") (pin "5") (pinfunction "S_5") (pintype "passive"))
    )
    (net (code "49") (name "MV_COM") (class "Default")
      (node (ref "K1") (pin "CENTER1") (pinfunction "P_CENTER1") (pintype "passive"))
      (node (ref "K1") (pin "CENTER2") (pinfunction "P2_CENTER2") (pintype "bidirectional"))
      (node (ref "K10") (pin "CENTER1") (pinfunction "P_CENTER1") (pintype "passive"))
      (node (ref "K10") (pin "CENTER2") (pinfunction "P2_CENTER2") (pintype "bidirectional"))
      (node (ref "K2") (pin "CENTER1") (pinfunction "P_CENTER1") (pintype "passive"))
      (node (ref "K2") (pin "CENTER2") (pinfunction "P2_CENTER2") (pintype "bidirectional"))
      (node (ref "K3") (pin "CENTER1") (pinfunction "P_CENTER1") (pintype "passive"))
      (node (ref "K3") (pin "CENTER2") (pinfunction "P2_CENTER2") (pintype "bidirectional"))
      (node (ref "K4") (pin "CENTER1") (pinfunction "P_CENTER1") (pintype "passive"))
      (node (ref "K4") (pin "CENTER2") (pinfunction "P2_CENTER2") (pintype "bidirectional"))
      (node (ref "K5") (pin "CENTER1") (pinfunction "P_CENTER1") (pintype "passive"))
      (node (ref "K5") (pin "CENTER2") (pinfunction "P2_CENTER2") (pintype "bidirectional"))
      (node (ref "K6") (pin "CENTER1") (pinfunction "P_CENTER1") (pintype "passive"))
      (node (ref "K6") (pin "CENTER2") (pinfunction "P2_CENTER2") (pintype "bidirectional"))
      (node (ref "K7") (pin "CENTER1") (pinfunction "P_CENTER1") (pintype "passive"))
      (node (ref "K7") (pin "CENTER2") (pinfunction "P2_CENTER2") (pintype "bidirectional"))
      (node (ref "K8") (pin "CENTER1") (pinfunction "P_CENTER1") (pintype "passive"))
      (node (ref "K8") (pin "CENTER2") (pinfunction "P2_CENTER2") (pintype "bidirectional"))
      (node (ref "K9") (pin "CENTER1") (pinfunction "P_CENTER1") (pintype "passive"))
      (node (ref "K9") (pin "CENTER2") (pinfunction "P2_CENTER2") (pintype "bidirectional"))
      (node (ref "X3") (pin "6") (pinfunction "S_6") (pintype "passive"))
    )
    (net (code "50") (name "Net-(IC2-(PCINT1{slash}ADC1)PA1)") (class "Default")
      (node (ref "IC2") (pin "36") (pinfunction "(PCINT1/ADC1)PA1_36") (pintype "bidirectional"))
      (node (ref "R3") (pin "1") (pinfunction "1_1") (pintype "passive"))
    )
    (net (code "51") (name "Net-(IC2-XTAL1)") (class "Default")
      (node (ref "C4") (pin "1") (pinfunction "1_1") (pintype "passive"))
      (node (ref "IC2") (pin "8") (pinfunction "XTAL1_8") (pintype "bidirectional"))
      (node (ref "Q1") (pin "3") (pinfunction "3_3") (pintype "passive"))
    )
    (net (code "52") (name "Net-(IC2-XTAL2)") (class "Default")
      (node (ref "C3") (pin "2") (pinfunction "2_2") (pintype "passive"))
      (node (ref "IC2") (pin "7") (pinfunction "XTAL2_7") (pintype "bidirectional"))
      (node (ref "Q1") (pin "1") (pinfunction "1_1") (pintype "passive"))
    )
    (net (code "53") (name "Net-(IC3-OSC1)") (class "Default")
      (node (ref "C6") (pin "1") (pinfunction "1_1") (pintype "passive"))
      (node (ref "IC3") (pin "8") (pinfunction "OSC1_8") (pintype "input"))
      (node (ref "Q2") (pin "3") (pinfunction "3_3") (pintype "passive"))
    )
    (net (code "54") (name "Net-(IC3-OSC2)") (class "Default")
      (node (ref "C5") (pin "2") (pinfunction "2_2") (pintype "passive"))
      (node (ref "IC3") (pin "7") (pinfunction "OSC2_7") (pintype "output"))
      (node (ref "Q2") (pin "1") (pinfunction "1_1") (pintype "passive"))
    )
    (net (code "55") (name "Net-(IC3-RESET)") (class "Default")
      (node (ref "IC3") (pin "17") (pinfunction "RESET_17") (pintype "input"))
      (node (ref "R2") (pin "1") (pinfunction "1_1") (pintype "passive"))
    )
    (net (code "56") (name "Net-(K11-P$3)") (class "Default")
      (node (ref "K11") (pin "11") (pinfunction "P$3_11") (pintype "passive"))
      (node (ref "X6") (pin "2") (pinfunction "KL_2") (pintype "passive"))
    )
    (net (code "57") (name "Net-(K11-P$4)") (class "Default")
      (node (ref "K11") (pin "14") (pinfunction "P$4_14") (pintype "passive"))
      (node (ref "X6") (pin "1") (pinfunction "KL_1") (pintype "passive"))
    )
    (net (code "58") (name "Net-(K11-P$5)") (class "Default")
      (node (ref "K11") (pin "12") (pinfunction "P$5_12") (pintype "passive"))
      (node (ref "X6") (pin "3") (pinfunction "KL_3") (pintype "passive"))
    )
    (net (code "59") (name "Net-(K12-P$3)") (class "Default")
      (node (ref "K12") (pin "11") (pinfunction "P$3_11") (pintype "passive"))
      (node (ref "X7") (pin "2") (pinfunction "KL_2") (pintype "passive"))
    )
    (net (code "60") (name "Net-(K12-P$4)") (class "Default")
      (node (ref "K12") (pin "14") (pinfunction "P$4_14") (pintype "passive"))
      (node (ref "X7") (pin "1") (pinfunction "KL_1") (pintype "passive"))
    )
    (net (code "61") (name "Net-(K12-P$5)") (class "Default")
      (node (ref "K12") (pin "12") (pinfunction "P$5_12") (pintype "passive"))
      (node (ref "X7") (pin "3") (pinfunction "KL_3") (pintype "passive"))
    )
    (net (code "62") (name "Net-(LED1-PadA)") (class "Default")
      (node (ref "LED1") (pin "A") (pinfunction "A_A") (pintype "passive"))
      (node (ref "R8") (pin "2") (pinfunction "2_2") (pintype "passive"))
    )
    (net (code "63") (name "Net-(LED2-PadA)") (class "Default")
      (node (ref "LED2") (pin "A") (pinfunction "A_A") (pintype "passive"))
      (node (ref "R9") (pin "2") (pinfunction "2_2") (pintype "passive"))
    )
    (net (code "64") (name "Net-(LED3-PadA)") (class "Default")
      (node (ref "LED3") (pin "A") (pinfunction "A_A") (pintype "passive"))
      (node (ref "R10") (pin "2") (pinfunction "2_2") (pintype "passive"))
    )
    (net (code "65") (name "Net-(LED4-PadA)") (class "Default")
      (node (ref "LED4") (pin "A") (pinfunction "A_A") (pintype "passive"))
      (node (ref "R11") (pin "2") (pinfunction "2_2") (pintype "passive"))
    )
    (net (code "66") (name "Net-(LED5-PadA)") (class "Default")
      (node (ref "LED5") (pin "A") (pinfunction "A_A") (pintype "passive"))
      (node (ref "R12") (pin "2") (pinfunction "2_2") (pintype "passive"))
    )
    (net (code "67") (name "Net-(LED6-PadA)") (class "Default")
      (node (ref "LED6") (pin "A") (pinfunction "A_A") (pintype "passive"))
      (node (ref "R13") (pin "2") (pinfunction "2_2") (pintype "passive"))
    )
    (net (code "68") (name "Net-(LED7-PadA)") (class "Default")
      (node (ref "LED7") (pin "A") (pinfunction "A_A") (pintype "passive"))
      (node (ref "R14") (pin "2") (pinfunction "2_2") (pintype "passive"))
    )
    (net (code "69") (name "Net-(LED8-PadA)") (class "Default")
      (node (ref "LED8") (pin "A") (pinfunction "A_A") (pintype "passive"))
      (node (ref "R15") (pin "2") (pinfunction "2_2") (pintype "passive"))
    )
    (net (code "70") (name "Net-(LED9-PadA)") (class "Default")
      (node (ref "LED9") (pin "A") (pinfunction "A_A") (pintype "passive"))
      (node (ref "R16") (pin "2") (pinfunction "2_2") (pintype "passive"))
    )
    (net (code "71") (name "Net-(LED10-PadA)") (class "Default")
      (node (ref "LED10") (pin "A") (pinfunction "A_A") (pintype "passive"))
      (node (ref "R17") (pin "2") (pinfunction "2_2") (pintype "passive"))
    )
    (net (code "72") (name "Net-(LED11-PadA)") (class "Default")
      (node (ref "LED11") (pin "A") (pinfunction "A_A") (pintype "passive"))
      (node (ref "R18") (pin "2") (pinfunction "2_2") (pintype "passive"))
    )
    (net (code "73") (name "Net-(LED12-PadA)") (class "Default")
      (node (ref "LED12") (pin "A") (pinfunction "A_A") (pintype "passive"))
      (node (ref "R19") (pin "2") (pinfunction "2_2") (pintype "passive"))
    )
    (net (code "74") (name "Net-(LED13-PadA)") (class "Default")
      (node (ref "LED13") (pin "A") (pinfunction "A_A") (pintype "passive"))
      (node (ref "R3") (pin "2") (pinfunction "2_2") (pintype "passive"))
    )
    (net (code "75") (name "OUT1") (class "Default")
      (node (ref "IC2") (pin "15") (pinfunction "(PCINT30/OC2B/ICP)PD6_15") (pintype "bidirectional"))
      (node (ref "IC5") (pin "7") (pinfunction "I7_7") (pintype "input"))
      (node (ref "R8") (pin "1") (pinfunction "1_1") (pintype "passive"))
    )
    (net (code "76") (name "OUT2") (class "Default")
      (node (ref "IC2") (pin "16") (pinfunction "(PCINT31/OC2A)PD7_16") (pintype "bidirectional"))
      (node (ref "IC5") (pin "6") (pinfunction "I6_6") (pintype "input"))
      (node (ref "R9") (pin "1") (pinfunction "1_1") (pintype "passive"))
    )
    (net (code "77") (name "OUT3") (class "Default")
      (node (ref "IC2") (pin "21") (pinfunction "(PCINT18/TCK)PC2_21") (pintype "output"))
      (node (ref "IC5") (pin "5") (pinfunction "I5_5") (pintype "input"))
      (node (ref "R10") (pin "1") (pinfunction "1_1") (pintype "passive"))
    )
    (net (code "78") (name "OUT4") (class "Default")
      (node (ref "IC2") (pin "22") (pinfunction "(PCINT19/TMS)PC3_22") (pintype "output"))
      (node (ref "IC5") (pin "4") (pinfunction "I4_4") (pintype "input"))
      (node (ref "R11") (pin "1") (pinfunction "1_1") (pintype "passive"))
    )
    (net (code "79") (name "OUT5") (class "Default")
      (node (ref "IC2") (pin "23") (pinfunction "(PCINT20/TDO)PC4_23") (pintype "output"))
      (node (ref "IC5") (pin "3") (pinfunction "I3_3") (pintype "input"))
      (node (ref "R12") (pin "1") (pinfunction "1_1") (pintype "passive"))
    )
    (net (code "80") (name "OUT6") (class "Default")
      (node (ref "IC2") (pin "24") (pinfunction "(PCINT21/TDI)PC5_24") (pintype "output"))
      (node (ref "IC5") (pin "2") (pinfunction "I2_2") (pintype "input"))
      (node (ref "R13") (pin "1") (pinfunction "1_1") (pintype "passive"))
    )
    (net (code "81") (name "OUT7") (class "Default")
      (node (ref "IC2") (pin "25") (pinfunction "(PCINT22/TOSC1)PC6_25") (pintype "output"))
      (node (ref "IC5") (pin "1") (pinfunction "I1_1") (pintype "input"))
      (node (ref "R14") (pin "1") (pinfunction "1_1") (pintype "passive"))
    )
    (net (code "82") (name "OUT8") (class "Default")
      (node (ref "IC2") (pin "26") (pinfunction "(PCINT23/TOSC2)PC7_26") (pintype "output"))
      (node (ref "IC6") (pin "7") (pinfunction "I7_7") (pintype "input"))
      (node (ref "R15") (pin "1") (pinfunction "1_1") (pintype "passive"))
    )
    (net (code "83") (name "OUT9") (class "Default")
      (node (ref "IC2") (pin "30") (pinfunction "(PCINT7/ADC7)PA7_30") (pintype "bidirectional"))
      (node (ref "IC6") (pin "6") (pinfunction "I6_6") (pintype "input"))
      (node (ref "R16") (pin "1") (pinfunction "1_1") (pintype "passive"))
    )
    (net (code "84") (name "OUT10") (class "Default")
      (node (ref "IC2") (pin "31") (pinfunction "(PCINT6/ADC6)PA6_31") (pintype "bidirectional"))
      (node (ref "IC6") (pin "5") (pinfunction "I5_5") (pintype "input"))
      (node (ref "R17") (pin "1") (pinfunction "1_1") (pintype "passive"))
    )
    (net (code "85") (name "OUT11") (class "Default")
      (node (ref "IC2") (pin "32") (pinfunction "(PCINT5/ADC5)PA5_32") (pintype "bidirectional"))
      (node (ref "IC6") (pin "2") (pinfunction "I2_2") (pintype "input"))
      (node (ref "R18") (pin "1") (pinfunction "1_1") (pintype "passive"))
    )
    (net (code "86") (name "OUT12") (class "Default")
      (node (ref "IC2") (pin "33") (pinfunction "(PCINT4/ADC4)PA4_33") (pintype "bidirectional"))
      (node (ref "IC6") (pin "1") (pinfunction "I1_1") (pintype "input"))
      (node (ref "R19") (pin "1") (pinfunction "1_1") (pintype "passive"))
    )
    (net (code "87") (name "OUT_LED_1") (class "Default")
      (node (ref "IC2") (pin "34") (pinfunction "(PCINT3/ADC3)PA3_34") (pintype "bidirectional"))
      (node (ref "IC6") (pin "3") (pinfunction "I3_3") (pintype "input"))
    )
    (net (code "88") (name "OUT_LED_2") (class "Default")
      (node (ref "IC2") (pin "35") (pinfunction "(PCINT2/ADC2)PA2_35") (pintype "bidirectional"))
      (node (ref "IC6") (pin "4") (pinfunction "I4_4") (pintype "input"))
    )
    (net (code "89") (name "RELAIS_1") (class "Default")
      (node (ref "IC5") (pin "10") (pinfunction "O7_10") (pintype "open_collector"))
      (node (ref "K1") (pin "COIL2") (pinfunction "2_COIL2") (pintype "passive"))
    )
    (net (code "90") (name "RELAIS_2") (class "Default")
      (node (ref "IC5") (pin "11") (pinfunction "O6_11") (pintype "open_collector"))
      (node (ref "K2") (pin "COIL2") (pinfunction "2_COIL2") (pintype "passive"))
    )
    (net (code "91") (name "RELAIS_3") (class "Default")
      (node (ref "IC5") (pin "12") (pinfunction "O5_12") (pintype "open_collector"))
      (node (ref "K3") (pin "COIL2") (pinfunction "2_COIL2") (pintype "passive"))
    )
    (net (code "92") (name "RELAIS_4") (class "Default")
      (node (ref "IC5") (pin "13") (pinfunction "O4_13") (pintype "open_collector"))
      (node (ref "K4") (pin "COIL2") (pinfunction "2_COIL2") (pintype "passive"))
    )
    (net (code "93") (name "RELAIS_5") (class "Default")
      (node (ref "IC5") (pin "14") (pinfunction "O3_14") (pintype "open_collector"))
      (node (ref "K5") (pin "COIL2") (pinfunction "2_COIL2") (pintype "passive"))
    )
    (net (code "94") (name "RELAIS_6") (class "Default")
      (node (ref "IC5") (pin "15") (pinfunction "O2_15") (pintype "open_collector"))
      (node (ref "K6") (pin "COIL2") (pinfunction "2_COIL2") (pintype "passive"))
    )
    (net (code "95") (name "RELAIS_7") (class "Default")
      (node (ref "IC5") (pin "16") (pinfunction "O1_16") (pintype "open_collector"))
      (node (ref "K7") (pin "COIL2") (pinfunction "2_COIL2") (pintype "passive"))
    )
    (net (code "96") (name "RELAIS_8") (class "Default")
      (node (ref "IC6") (pin "10") (pinfunction "O7_10") (pintype "open_collector"))
      (node (ref "K8") (pin "COIL2") (pinfunction "2_COIL2") (pintype "passive"))
    )
    (net (code "97") (name "RELAIS_9") (class "Default")
      (node (ref "IC6") (pin "11") (pinfunction "O6_11") (pintype "open_collector"))
      (node (ref "K9") (pin "COIL2") (pinfunction "2_COIL2") (pintype "passive"))
    )
    (net (code "98") (name "RELAIS_10") (class "Default")
      (node (ref "IC6") (pin "12") (pinfunction "O5_12") (pintype "open_collector"))
      (node (ref "K10") (pin "COIL2") (pinfunction "2_COIL2") (pintype "passive"))
    )
    (net (code "99") (name "RELAIS_11") (class "Default")
      (node (ref "IC6") (pin "15") (pinfunction "O2_15") (pintype "open_collector"))
      (node (ref "K11") (pin "A1") (pinfunction "P$1_A1") (pintype "passive"))
    )
    (net (code "100") (name "RELAIS_12") (class "Default")
      (node (ref "IC6") (pin "16") (pinfunction "O1_16") (pintype "open_collector"))
      (node (ref "K12") (pin "A1") (pinfunction "P$1_A1") (pintype "passive"))
    )
    (net (code "101") (name "RST") (class "Default")
      (node (ref "IC2") (pin "4") (pinfunction "RESET_4") (pintype "input"))
      (node (ref "ISP") (pin "RST") (pinfunction "RST_RST") (pintype "passive"))
      (node (ref "R1") (pin "1") (pinfunction "1_1") (pintype "passive"))
      (node (ref "S1") (pin "3") (pinfunction "S_3") (pintype "passive"))
      (node (ref "S1") (pin "4") (pinfunction "S1_4") (pintype "passive"))
    )
    (net (code "102") (name "RXCAN") (class "Default")
      (node (ref "IC3") (pin "2") (pinfunction "RXCAN_2") (pintype "input"))
      (node (ref "IC4") (pin "4") (pinfunction "RXD_4") (pintype "output"))
    )
    (net (code "103") (name "SCK") (class "Default")
      (node (ref "IC2") (pin "3") (pinfunction "(PCINT15/SCK)PB7_3") (pintype "bidirectional"))
      (node (ref "IC3") (pin "13") (pinfunction "SCK_13") (pintype "input"))
      (node (ref "ISP") (pin "SCK") (pinfunction "SCK_SCK") (pintype "passive"))
    )
    (net (code "104") (name "SCL") (class "Default")
      (node (ref "IC2") (pin "19") (pinfunction "(PCINT16/SCL)PC0_19") (pintype "output"))
      (node (ref "IC7") (pin "14") (pinfunction "SCL_14") (pintype "input"))
      (node (ref "IC8") (pin "14") (pinfunction "SCL_14") (pintype "input"))
      (node (ref "IC9") (pin "14") (pinfunction "SCL_14") (pintype "input"))
      (node (ref "R6") (pin "1") (pinfunction "1_1") (pintype "passive"))
      (node (ref "X12") (pin "4") (pinfunction "S_4") (pintype "passive"))
    )
    (net (code "105") (name "SDA") (class "Default")
      (node (ref "IC2") (pin "20") (pinfunction "(PCINT17/SDA)PC1_20") (pintype "output"))
      (node (ref "IC7") (pin "15") (pinfunction "SDA_15") (pintype "bidirectional"))
      (node (ref "IC8") (pin "15") (pinfunction "SDA_15") (pintype "bidirectional"))
      (node (ref "IC9") (pin "15") (pinfunction "SDA_15") (pintype "bidirectional"))
      (node (ref "R5") (pin "1") (pinfunction "1_1") (pintype "passive"))
      (node (ref "X12") (pin "3") (pinfunction "S_3") (pintype "passive"))
    )
    (net (code "106") (name "TXCAN") (class "Default")
      (node (ref "IC3") (pin "1") (pinfunction "TXCAN_1") (pintype "output"))
      (node (ref "IC4") (pin "1") (pinfunction "TXD_1") (pintype "input"))
    )
    (net (code "107") (name "unconnected-(IC2-(PCINT0{slash}ADC0)PA0-Pad37)") (class "Default")
      (node (ref "IC2") (pin "37") (pinfunction "(PCINT0/ADC0)PA0_37") (pintype "bidirectional"))
    )
    (net (code "108") (name "unconnected-(IC2-(PCINT8{slash}XCK0{slash}T0)PB0-Pad40)") (class "Default")
      (node (ref "IC2") (pin "40") (pinfunction "(PCINT8/XCK0/T0)PB0_40") (pintype "bidirectional"))
    )
    (net (code "109") (name "unconnected-(IC2-(PCINT9{slash}CLKO{slash}T1)PB1-Pad41)") (class "Default")
      (node (ref "IC2") (pin "41") (pinfunction "(PCINT9/CLKO/T1)PB1_41") (pintype "bidirectional"))
    )
    (net (code "110") (name "unconnected-(IC2-(PCINT10{slash}INT2{slash}AIN0)PB2-Pad42)") (class "Default")
      (node (ref "IC2") (pin "42") (pinfunction "(PCINT10/INT2/AIN0)PB2_42") (pintype "bidirectional"))
    )
    (net (code "111") (name "unconnected-(IC2-(PCINT11{slash}OC0A{slash}AIN1)PB3-Pad43)") (class "Default")
      (node (ref "IC2") (pin "43") (pinfunction "(PCINT11/OC0A/AIN1)PB3_43") (pintype "bidirectional"))
    )
    (net (code "112") (name "unconnected-(IC2-(PCINT24{slash}RXD0)PD0-Pad9)") (class "Default")
      (node (ref "IC2") (pin "9") (pinfunction "(PCINT24/RXD0)PD0_9") (pintype "bidirectional"))
    )
    (net (code "113") (name "unconnected-(IC2-(PCINT25{slash}TXD0)PD1-Pad10)") (class "Default")
      (node (ref "IC2") (pin "10") (pinfunction "(PCINT25/TXD0)PD1_10") (pintype "bidirectional"))
    )
    (net (code "114") (name "unconnected-(IC2-(PCINT28{slash}OC1B)PD4-Pad13)") (class "Default")
      (node (ref "IC2") (pin "13") (pinfunction "(PCINT28/OC1B)PD4_13") (pintype "bidirectional"))
    )
    (net (code "115") (name "unconnected-(IC2-AREF-Pad29)") (class "Default")
      (node (ref "IC2") (pin "29") (pinfunction "AREF_29") (pintype "passive"))
    )
    (net (code "116") (name "unconnected-(IC3-CLKOUT-Pad3)") (class "Default")
      (node (ref "IC3") (pin "3") (pinfunction "CLKOUT_3") (pintype "output"))
    )
    (net (code "117") (name "unconnected-(IC3-RX0BF-Pad11)") (class "Default")
      (node (ref "IC3") (pin "11") (pinfunction "RX0BF_11") (pintype "output"))
    )
    (net (code "118") (name "unconnected-(IC3-RX1BF-Pad10)") (class "Default")
      (node (ref "IC3") (pin "10") (pinfunction "RX1BF_10") (pintype "output"))
    )
    (net (code "119") (name "unconnected-(IC3-TX0RTS-Pad4)") (class "Default")
      (node (ref "IC3") (pin "4") (pinfunction "TX0RTS_4") (pintype "input"))
    )
    (net (code "120") (name "unconnected-(IC3-TX1RTS-Pad5)") (class "Default")
      (node (ref "IC3") (pin "5") (pinfunction "TX1RTS_5") (pintype "input"))
    )
    (net (code "121") (name "unconnected-(IC3-TX2RTS-Pad6)") (class "Default")
      (node (ref "IC3") (pin "6") (pinfunction "TX2RTS_6") (pintype "input"))
    )
    (net (code "122") (name "unconnected-(K1B-O-PadCON2OPTION)") (class "Default")
      (node (ref "K1") (pin "CON2OPTION") (pinfunction "O_CON2OPTION") (pintype "passive"))
    )
    (net (code "123") (name "unconnected-(K2B-O-PadCON2OPTION)") (class "Default")
      (node (ref "K2") (pin "CON2OPTION") (pinfunction "O_CON2OPTION") (pintype "passive"))
    )
    (net (code "124") (name "unconnected-(K3B-O-PadCON2OPTION)") (class "Default")
      (node (ref "K3") (pin "CON2OPTION") (pinfunction "O_CON2OPTION") (pintype "passive"))
    )
    (net (code "125") (name "unconnected-(K4B-O-PadCON2OPTION)") (class "Default")
      (node (ref "K4") (pin "CON2OPTION") (pinfunction "O_CON2OPTION") (pintype "passive"))
    )
    (net (code "126") (name "unconnected-(K5B-O-PadCON2OPTION)") (class "Default")
      (node (ref "K5") (pin "CON2OPTION") (pinfunction "O_CON2OPTION") (pintype "passive"))
    )
    (net (code "127") (name "unconnected-(K6B-O-PadCON2OPTION)") (class "Default")
      (node (ref "K6") (pin "CON2OPTION") (pinfunction "O_CON2OPTION") (pintype "passive"))
    )
    (net (code "128") (name "unconnected-(K7B-O-PadCON2OPTION)") (class "Default")
      (node (ref "K7") (pin "CON2OPTION") (pinfunction "O_CON2OPTION") (pintype "passive"))
    )
    (net (code "129") (name "unconnected-(K8B-O-PadCON2OPTION)") (class "Default")
      (node (ref "K8") (pin "CON2OPTION") (pinfunction "O_CON2OPTION") (pintype "passive"))
    )
    (net (code "130") (name "unconnected-(K9B-O-PadCON2OPTION)") (class "Default")
      (node (ref "K9") (pin "CON2OPTION") (pinfunction "O_CON2OPTION") (pintype "passive"))
    )
    (net (code "131") (name "unconnected-(K10B-O-PadCON2OPTION)") (class "Default")
      (node (ref "K10") (pin "CON2OPTION") (pinfunction "O_CON2OPTION") (pintype "passive"))
    )
  )
)
